# SAM_Dispenser_1.net
KiCad netlist of a schematic drawn in Altium Designer
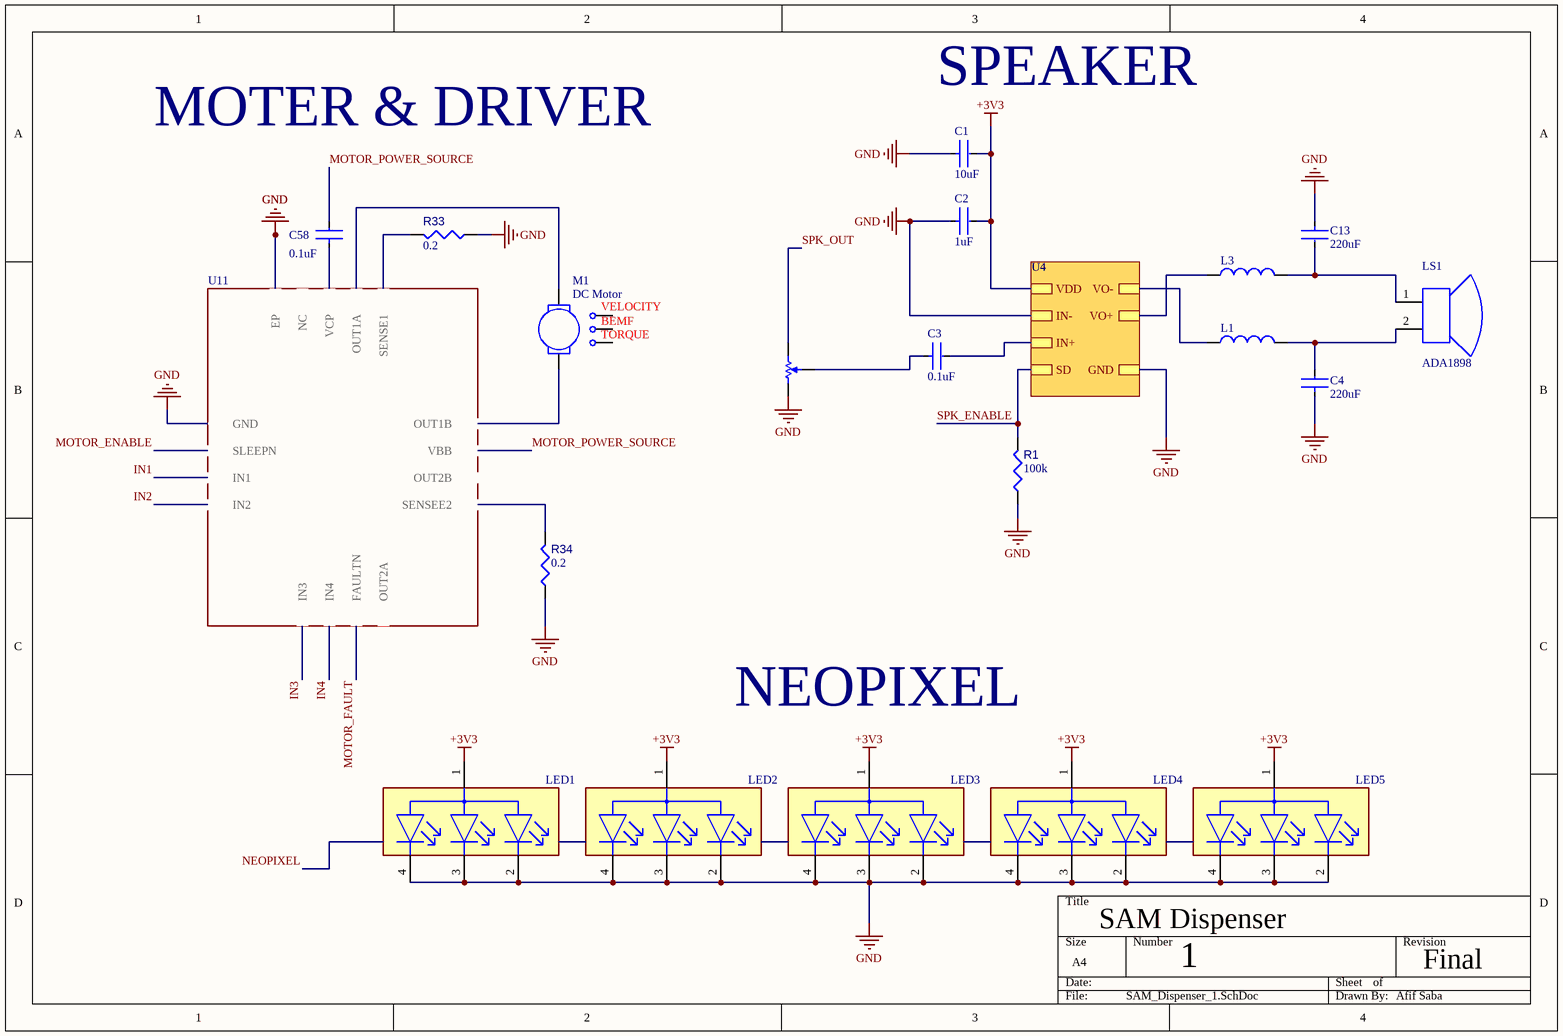
[diagram p0: SAM_Dispenser_1.SchDoc]

(export (version "E")
  (design (tool "Eeschema 10.0.6"))
  (components
    (comp (ref "C1")
      (value "475CKE400M")
      (footprint "4.7uF400V")
      (description "4.7 µF 400 V Aluminum Electrolytic Capacitors Radial, Can 70.547Ohm @ 120Hz 2000 Hrs @ 105°C")
      (fields (field (name "PARAMETER 1") "10uF"))
      (libsource (lib "UNB Workspace") (part "Symbol"))
    )
    (comp (ref "C2")
      (value "475CKE400M")
      (footprint "4.7uF400V")
      (description "4.7 µF 400 V Aluminum Electrolytic Capacitors Radial, Can 70.547Ohm @ 120Hz 2000 Hrs @ 105°C")
      (fields (field (name "PARAMETER 1") "1uF"))
      (libsource (lib "UNB Workspace") (part "Symbol"))
    )
    (comp (ref "C3")
      (value "475CKE400M")
      (footprint "4.7uF400V")
      (description "4.7 µF 400 V Aluminum Electrolytic Capacitors Radial, Can 70.547Ohm @ 120Hz 2000 Hrs @ 105°C")
      (fields (field (name "PARAMETER 1") "0.1uF"))
      (libsource (lib "UNB Workspace") (part "Symbol"))
    )
    (comp (ref "C4")
      (value "475CKE400M")
      (footprint "4.7uF400V")
      (description "4.7 µF 400 V Aluminum Electrolytic Capacitors Radial, Can 70.547Ohm @ 120Hz 2000 Hrs @ 105°C")
      (fields (field (name "PARAMETER 1") "220uF"))
      (libsource (lib "UNB Workspace") (part "Symbol"))
    )
    (comp (ref "C13")
      (value "475CKE400M")
      (footprint "4.7uF400V")
      (description "4.7 µF 400 V Aluminum Electrolytic Capacitors Radial, Can 70.547Ohm @ 120Hz 2000 Hrs @ 105°C")
      (fields (field (name "PARAMETER 1") "220uF"))
      (libsource (lib "UNB Workspace") (part "Symbol"))
    )
    (comp (ref "C58")
      (value "475CKE400M")
      (footprint "4.7uF400V")
      (description "4.7 µF 400 V Aluminum Electrolytic Capacitors Radial, Can 70.547Ohm @ 120Hz 2000 Hrs @ 105°C")
      (fields (field (name "PARAMETER 1") "0.1uF"))
      (libsource (lib "UNB Workspace") (part "Symbol"))
    )
    (comp (ref "L1")
      (value "Inductor47pH")
      (footprint "WE-PD 1050")
      (libsource (lib "UNB Workspace") (part "Inductor47pH"))
    )
    (comp (ref "L3")
      (value "Inductor47pH")
      (footprint "WE-PD 1050")
      (libsource (lib "UNB Workspace") (part "Inductor47pH"))
    )
    (comp (ref "LED1")
      (value "SML-LX0404SIUPGUSB")
      (footprint "FP-SML-LX0404SIUPGUSB-MFG")
      (description "LED RGB CLEAR SMD")
      (libsource (lib "Altium Content Vault") (part "2e8871f6955a40d35a6a753e53ead77"))
    )
    (comp (ref "LED2")
      (value "SML-LX0404SIUPGUSB")
      (footprint "FP-SML-LX0404SIUPGUSB-MFG")
      (description "LED RGB CLEAR SMD")
      (libsource (lib "Altium Content Vault") (part "2e8871f6955a40d35a6a753e53ead77"))
    )
    (comp (ref "LED3")
      (value "SML-LX0404SIUPGUSB")
      (footprint "FP-SML-LX0404SIUPGUSB-MFG")
      (description "LED RGB CLEAR SMD")
      (libsource (lib "Altium Content Vault") (part "2e8871f6955a40d35a6a753e53ead77"))
    )
    (comp (ref "LED4")
      (value "SML-LX0404SIUPGUSB")
      (footprint "FP-SML-LX0404SIUPGUSB-MFG")
      (description "LED RGB CLEAR SMD")
      (libsource (lib "Altium Content Vault") (part "2e8871f6955a40d35a6a753e53ead77"))
    )
    (comp (ref "LED5")
      (value "SML-LX0404SIUPGUSB")
      (footprint "FP-SML-LX0404SIUPGUSB-MFG")
      (description "LED RGB CLEAR SMD")
      (libsource (lib "Altium Content Vault") (part "2e8871f6955a40d35a6a753e53ead77"))
    )
    (comp (ref "LS1")
      (value "ADA1898")
      (footprint "ADAI-ADA1898")
      (description "Mini Speaker, 8 Ohm, 0.2 Wmax, -10 to 40 degC, 2-Pin THD, RoHS")
      (fields (field (name "MANUFACTURER") "Adafruit Industries"))
      (libsource (lib "UNB Workspace") (part "SPEAKER-2"))
    )
    (comp (ref "M1") (value "DC Motor") (libsource (lib "Simulation Generic Components") (part "DC Motor")))
    (comp (ref "R1")
      (value "100k")
      (footprint "RESC0402(1005)_L")
      (description "3K 0.063W 1% 0402 (1005 Metric)  SMD")
      (fields (field (name "POWER") "63mW") (field (name "TOLERANCE") "1%"))
      (libsource (lib "UNB Workspace") (part "3KR2F"))
    )
    (comp (ref "R2")
      (value "TC33X-2-103E")
      (footprint "BOUR-TC33X-2_V")
      (description "Trimming Potentiometer, 10000 Ohm, -40 to 100 degC, 3-Pin SMD, RoHS, Tape and Reel")
      (fields (field (name "POWER") "100mW") (field (name "TOLERANCE") "25%"))
      (libsource (lib "UNB Workspace") (part "RES-ADJ-3_A"))
    )
    (comp (ref "R33")
      (value "3KR2F")
      (footprint "RESC0402(1005)_L")
      (description "3K 0.063W 1% 0402 (1005 Metric)  SMD")
      (fields (field (name "POWER") "63mW") (field (name "TOLERANCE") "1%") (field (name "R34") "0.2"))
      (libsource (lib "UNB Workspace") (part "3KR2F"))
    )
    (comp (ref "R34")
      (value "3KR2F")
      (footprint "RESC0402(1005)_L")
      (description "3K 0.063W 1% 0402 (1005 Metric)  SMD")
      (fields (field (name "POWER") "63mW") (field (name "TOLERANCE") "1%") (field (name "R34") "0.2"))
      (libsource (lib "UNB Workspace") (part "3KR2F"))
    )
  )
  (nets
    (net (code "1") (name "+3V3") (class "Default")
      (node (ref "C1") (pin "2") (pinfunction "2_2") (pintype "passive"))
      (node (ref "C2") (pin "2") (pinfunction "2_2") (pintype "passive"))
      (node (ref "LED1") (pin "1") (pinfunction "Common_Anode_1") (pintype "passive"))
      (node (ref "LED2") (pin "1") (pinfunction "Common_Anode_1") (pintype "passive"))
      (node (ref "LED3") (pin "1") (pinfunction "Common_Anode_1") (pintype "passive"))
      (node (ref "LED4") (pin "1") (pinfunction "Common_Anode_1") (pintype "passive"))
      (node (ref "LED5") (pin "1") (pinfunction "Common_Anode_1") (pintype "passive"))
    )
    (net (code "2") (name "/IN+") (class "Default")
      (node (ref "C3") (pin "2") (pinfunction "2_2") (pintype "passive"))
    )
    (net (code "9") (name "/MOTOR_POWER_SOURCE") (class "Default")
      (node (ref "C58") (pin "2") (pinfunction "2_2") (pintype "passive"))
    )
    (net (code "12") (name "/OUT1A") (class "Default")
      (node (ref "M1") (pin "1") (pinfunction "1_1") (pintype "passive"))
    )
    (net (code "13") (name "/OUT1B") (class "Default")
      (node (ref "M1") (pin "2") (pinfunction "2_2") (pintype "passive"))
    )
    (net (code "16") (name "/SENSE1") (class "Default")
      (node (ref "R33") (pin "2") (pinfunction "2_2") (pintype "passive"))
    )
    (net (code "17") (name "/SENSEE2") (class "Default")
      (node (ref "R34") (pin "2") (pinfunction "2_2") (pintype "passive"))
    )
    (net (code "18") (name "/SPK_ENABLE") (class "Default")
      (node (ref "R1") (pin "2") (pinfunction "2_2") (pintype "passive"))
    )
    (net (code "19") (name "/SPK_OUT") (class "Default")
      (node (ref "R2") (pin "3") (pinfunction "3_3") (pintype "passive"))
    )
    (net (code "20") (name "/VCP") (class "Default")
      (node (ref "C58") (pin "1") (pinfunction "1_1") (pintype "passive"))
    )
    (net (code "21") (name "/VO+") (class "Default")
      (node (ref "L3") (pin "1") (pinfunction "1_1") (pintype "passive"))
    )
    (net (code "22") (name "/VO-") (class "Default")
      (node (ref "L1") (pin "1") (pinfunction "1_1") (pintype "passive"))
    )
    (net (code "23") (name "GND") (class "Default")
      (node (ref "C1") (pin "1") (pinfunction "1_1") (pintype "passive"))
      (node (ref "C13") (pin "1") (pinfunction "1_1") (pintype "passive"))
      (node (ref "C2") (pin "1") (pinfunction "1_1") (pintype "passive"))
      (node (ref "C4") (pin "1") (pinfunction "1_1") (pintype "passive"))
      (node (ref "LED1") (pin "2") (pinfunction "Red_C_2") (pintype "passive"))
      (node (ref "LED1") (pin "3") (pinfunction "Blue_C_3") (pintype "passive"))
      (node (ref "LED1") (pin "4") (pinfunction "Green_C_4") (pintype "passive"))
      (node (ref "LED2") (pin "2") (pinfunction "Red_C_2") (pintype "passive"))
      (node (ref "LED2") (pin "3") (pinfunction "Blue_C_3") (pintype "passive"))
      (node (ref "LED2") (pin "4") (pinfunction "Green_C_4") (pintype "passive"))
      (node (ref "LED3") (pin "2") (pinfunction "Red_C_2") (pintype "passive"))
      (node (ref "LED3") (pin "3") (pinfunction "Blue_C_3") (pintype "passive"))
      (node (ref "LED3") (pin "4") (pinfunction "Green_C_4") (pintype "passive"))
      (node (ref "LED4") (pin "2") (pinfunction "Red_C_2") (pintype "passive"))
      (node (ref "LED4") (pin "3") (pinfunction "Blue_C_3") (pintype "passive"))
      (node (ref "LED4") (pin "4") (pinfunction "Green_C_4") (pintype "passive"))
      (node (ref "LED5") (pin "2") (pinfunction "Red_C_2") (pintype "passive"))
      (node (ref "LED5") (pin "3") (pinfunction "Blue_C_3") (pintype "passive"))
      (node (ref "LED5") (pin "4") (pinfunction "Green_C_4") (pintype "passive"))
      (node (ref "R1") (pin "1") (pinfunction "1_1") (pintype "passive"))
      (node (ref "R2") (pin "1") (pinfunction "1_1") (pintype "passive"))
      (node (ref "R33") (pin "1") (pinfunction "1_1") (pintype "passive"))
      (node (ref "R34") (pin "1") (pinfunction "1_1") (pintype "passive"))
    )
    (net (code "24") (name "Net-(C3-Pad1)") (class "Default")
      (node (ref "C3") (pin "1") (pinfunction "1_1") (pintype "passive"))
      (node (ref "R2") (pin "2") (pinfunction "2_2") (pintype "passive"))
    )
    (net (code "25") (name "Net-(LS1-+)") (class "Default")
      (node (ref "C13") (pin "2") (pinfunction "2_2") (pintype "passive"))
      (node (ref "L3") (pin "2") (pinfunction "2_2") (pintype "passive"))
      (node (ref "LS1") (pin "1") (pinfunction "+_1") (pintype "passive"))
    )
    (net (code "26") (name "Net-(LS1--)") (class "Default")
      (node (ref "C4") (pin "2") (pinfunction "2_2") (pintype "passive"))
      (node (ref "L1") (pin "2") (pinfunction "2_2") (pintype "passive"))
      (node (ref "LS1") (pin "2") (pinfunction "-_2") (pintype "passive"))
    )
    (net (code "27") (name "unconnected-(M1-Pad3)") (class "Default")
      (node (ref "M1") (pin "3") (pinfunction "3_3") (pintype "passive"))
    )
    (net (code "28") (name "unconnected-(M1-Pad4)") (class "Default")
      (node (ref "M1") (pin "4") (pinfunction "4_4") (pintype "passive"))
    )
    (net (code "29") (name "unconnected-(M1-Pad5)") (class "Default")
      (node (ref "M1") (pin "5") (pinfunction "5_5") (pintype "passive"))
    )
  )
)
